# serial.net
KiCad netlist of a schematic drawn in Altium Designer
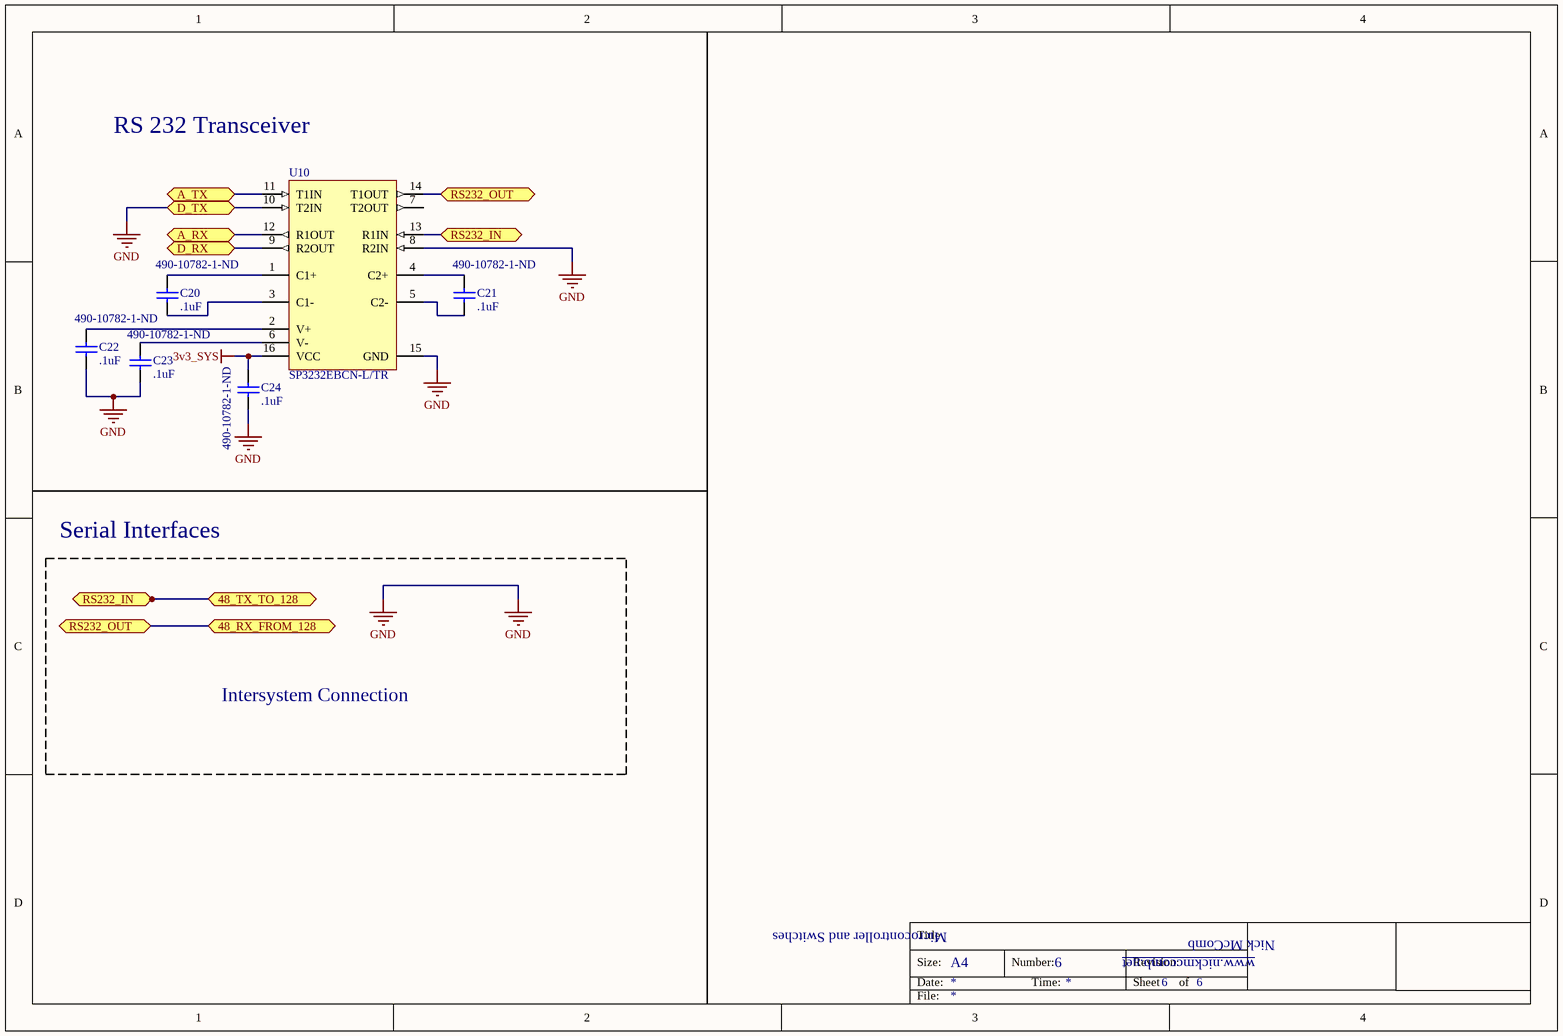
[diagram p0: serial.SchDoc]

(export (version "E")
  (design (tool "Eeschema 10.0.6"))
  (components
    (comp (ref "C20")
      (value ".1uF")
      (footprint "C0805")
      (description "Capacitor")
      (fields
        (field (name "SUPPLIER PART NUMBER 1") "490-10782-1-ND")
        (field (name "MANUFACTURER") "Murata Electronics North America")
        (field (name "MANUFACTURER PART NUMBER") "GRM21BR71H104JA01L")
        (field (name "PUBLISHER") "Altium Limited")
      )
      (libsource (lib "MultiAdapterLib") (part "Cap"))
    )
    (comp (ref "C21")
      (value ".1uF")
      (footprint "C0805")
      (description "Capacitor")
      (fields
        (field (name "SUPPLIER PART NUMBER 1") "490-10782-1-ND")
        (field (name "MANUFACTURER") "Murata Electronics North America")
        (field (name "MANUFACTURER PART NUMBER") "GRM21BR71H104JA01L")
        (field (name "PUBLISHER") "Altium Limited")
      )
      (libsource (lib "MultiAdapterLib") (part "Cap"))
    )
    (comp (ref "C22")
      (value ".1uF")
      (footprint "C0805")
      (description "Capacitor")
      (fields
        (field (name "SUPPLIER PART NUMBER 1") "490-10782-1-ND")
        (field (name "MANUFACTURER") "Murata Electronics North America")
        (field (name "MANUFACTURER PART NUMBER") "GRM21BR71H104JA01L")
        (field (name "PUBLISHER") "Altium Limited")
      )
      (libsource (lib "MultiAdapterLib") (part "Cap"))
    )
    (comp (ref "C23")
      (value ".1uF")
      (footprint "C0805")
      (description "Capacitor")
      (fields
        (field (name "SUPPLIER PART NUMBER 1") "490-10782-1-ND")
        (field (name "MANUFACTURER") "Murata Electronics North America")
        (field (name "MANUFACTURER PART NUMBER") "GRM21BR71H104JA01L")
        (field (name "PUBLISHER") "Altium Limited")
      )
      (libsource (lib "MultiAdapterLib") (part "Cap"))
    )
    (comp (ref "C24")
      (value ".1uF")
      (footprint "C0805")
      (description "Capacitor")
      (fields
        (field (name "SUPPLIER PART NUMBER 1") "490-10782-1-ND")
        (field (name "MANUFACTURER") "Murata Electronics North America")
        (field (name "MANUFACTURER PART NUMBER") "GRM21BR71H104JA01L")
        (field (name "PUBLISHER") "Altium Limited")
      )
      (libsource (lib "MultiAdapterLib") (part "Cap"))
    )
    (comp (ref "U10")
      (value "SP3232EBCN-L/TR")
      (footprint "EXAR-NSOIC-16_N")
      (fields (field (name "MANUFACTURER") "Exar Corporation"))
      (libsource (lib "Altium Content Vault") (part "EXAR-SP3232EB-16"))
    )
  )
  (nets
    (net (code "1") (name "/48_RX_FROM_128") (class "Default")
      (node (ref "U10") (pin "14") (pinfunction "T1OUT_14") (pintype "output"))
    )
    (net (code "3") (name "/A_RX") (class "Default")
      (node (ref "U10") (pin "12") (pinfunction "R1OUT_12") (pintype "output"))
    )
    (net (code "4") (name "/A_TX") (class "Default")
      (node (ref "U10") (pin "11") (pinfunction "T1IN_11") (pintype "input"))
    )
    (net (code "5") (name "/D_RX") (class "Default")
      (node (ref "U10") (pin "9") (pinfunction "R2OUT_9") (pintype "output"))
    )
    (net (code "6") (name "/RS232_IN") (class "Default")
      (node (ref "U10") (pin "13") (pinfunction "R1IN_13") (pintype "input"))
    )
    (net (code "7") (name "3v3_SYS") (class "Default")
      (node (ref "C24") (pin "2") (pinfunction "2_2") (pintype "passive"))
      (node (ref "U10") (pin "16") (pinfunction "VCC_16") (pintype "power_in"))
    )
    (net (code "8") (name "GND") (class "Default")
      (node (ref "C22") (pin "1") (pinfunction "1_1") (pintype "passive"))
      (node (ref "C23") (pin "1") (pinfunction "1_1") (pintype "passive"))
      (node (ref "C24") (pin "1") (pinfunction "1_1") (pintype "passive"))
      (node (ref "U10") (pin "10") (pinfunction "T2IN_10") (pintype "input"))
      (node (ref "U10") (pin "15") (pinfunction "GND_15") (pintype "power_in"))
      (node (ref "U10") (pin "8") (pinfunction "R2IN_8") (pintype "input"))
    )
    (net (code "9") (name "Net-(U10-C1+)") (class "Default")
      (node (ref "C20") (pin "2") (pinfunction "2_2") (pintype "passive"))
      (node (ref "U10") (pin "1") (pinfunction "C1+_1") (pintype "passive"))
    )
    (net (code "10") (name "Net-(U10-C1-)") (class "Default")
      (node (ref "C20") (pin "1") (pinfunction "1_1") (pintype "passive"))
      (node (ref "U10") (pin "3") (pinfunction "C1-_3") (pintype "passive"))
    )
    (net (code "11") (name "Net-(U10-C2+)") (class "Default")
      (node (ref "C21") (pin "2") (pinfunction "2_2") (pintype "passive"))
      (node (ref "U10") (pin "4") (pinfunction "C2+_4") (pintype "passive"))
    )
    (net (code "12") (name "Net-(U10-C2-)") (class "Default")
      (node (ref "C21") (pin "1") (pinfunction "1_1") (pintype "passive"))
      (node (ref "U10") (pin "5") (pinfunction "C2-_5") (pintype "passive"))
    )
    (net (code "13") (name "Net-(U10-V+)") (class "Default")
      (node (ref "C22") (pin "2") (pinfunction "2_2") (pintype "passive"))
      (node (ref "U10") (pin "2") (pinfunction "V+_2") (pintype "power_in"))
    )
    (net (code "14") (name "Net-(U10-V-)") (class "Default")
      (node (ref "C23") (pin "2") (pinfunction "2_2") (pintype "passive"))
      (node (ref "U10") (pin "6") (pinfunction "V-_6") (pintype "power_in"))
    )
    (net (code "15") (name "unconnected-(U10-T2OUT-Pad7)") (class "Default")
      (node (ref "U10") (pin "7") (pinfunction "T2OUT_7") (pintype "output"))
    )
  )
)
